# captivate_iso.net
KiCad netlist of a schematic drawn in Altium Designer
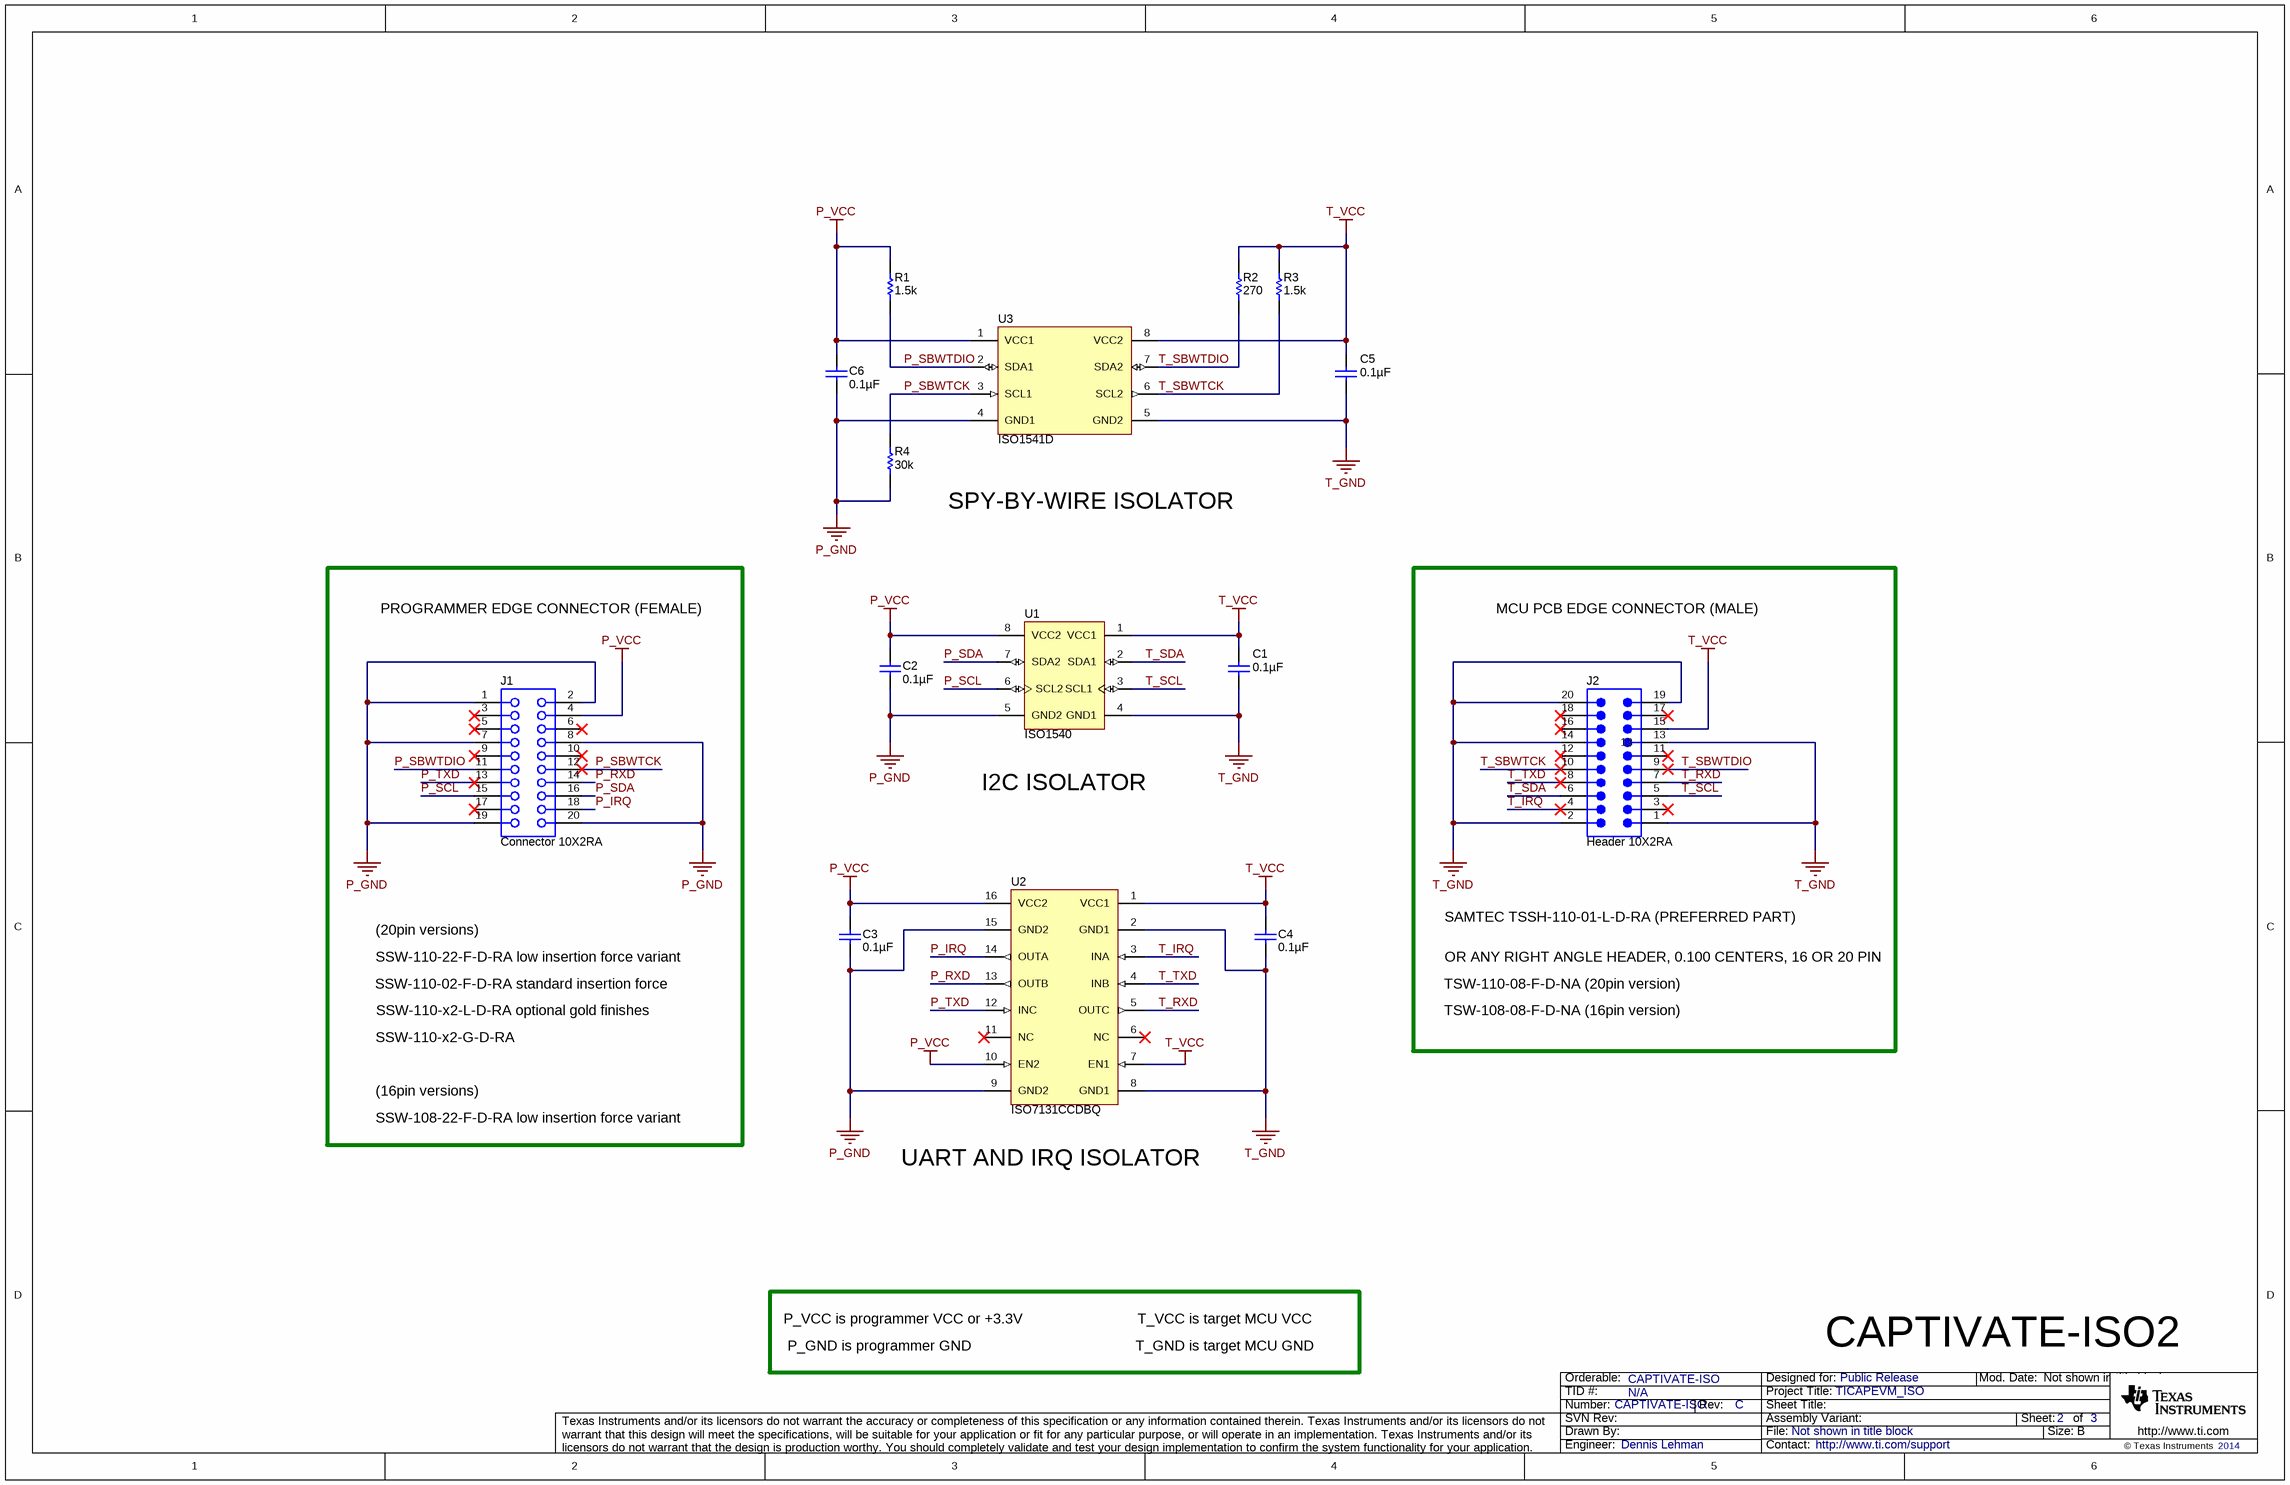
[diagram p0: captivate_iso.SchDoc]

(export (version "E")
  (design (tool "Eeschema 10.0.6"))
  (components
    (comp (ref "C1")
      (value "C1005X5R1A104K")
      (footprint "0402")
      (description "CAP, CERM, 0.1 µF, 10 V, +/- 10%, X5R, 0402")
      (fields
        (field (name "VALUEDISPLAYED") "0.1µF")
        (field (name "MANUFACTURER") "TDK")
        (field (name "PUBLISHER") "Texas Instruments")
      )
      (libsource (lib "Capacitor_Ceramic") (part "C1005X5R1A104K"))
    )
    (comp (ref "C2")
      (value "C1005X5R1A104K")
      (footprint "0402")
      (description "CAP, CERM, 0.1 µF, 10 V, +/- 10%, X5R, 0402")
      (fields
        (field (name "VALUEDISPLAYED") "0.1µF")
        (field (name "MANUFACTURER") "TDK")
        (field (name "PUBLISHER") "Texas Instruments")
      )
      (libsource (lib "Capacitor_Ceramic") (part "C1005X5R1A104K"))
    )
    (comp (ref "C3")
      (value "C1005X5R1A104K")
      (footprint "0402")
      (description "CAP, CERM, 0.1 µF, 10 V, +/- 10%, X5R, 0402")
      (fields
        (field (name "VALUEDISPLAYED") "0.1µF")
        (field (name "MANUFACTURER") "TDK")
        (field (name "PUBLISHER") "Texas Instruments")
      )
      (libsource (lib "Capacitor_Ceramic") (part "C1005X5R1A104K"))
    )
    (comp (ref "C4")
      (value "C1005X5R1A104K")
      (footprint "0402")
      (description "CAP, CERM, 0.1 µF, 10 V, +/- 10%, X5R, 0402")
      (fields
        (field (name "VALUEDISPLAYED") "0.1µF")
        (field (name "MANUFACTURER") "TDK")
        (field (name "PUBLISHER") "Texas Instruments")
      )
      (libsource (lib "Capacitor_Ceramic") (part "C1005X5R1A104K"))
    )
    (comp (ref "C5")
      (value "C1005X5R1A104K")
      (footprint "0402")
      (description "CAP, CERM, 0.1 µF, 10 V, +/- 10%, X5R, 0402")
      (fields
        (field (name "VALUEDISPLAYED") "0.1µF")
        (field (name "MANUFACTURER") "TDK")
        (field (name "PUBLISHER") "Texas Instruments")
      )
      (libsource (lib "Capacitor_Ceramic") (part "C1005X5R1A104K"))
    )
    (comp (ref "C6")
      (value "C1005X5R1A104K")
      (footprint "0402")
      (description "CAP, CERM, 0.1 µF, 10 V, +/- 10%, X5R, 0402")
      (fields
        (field (name "VALUEDISPLAYED") "0.1µF")
        (field (name "MANUFACTURER") "TDK")
        (field (name "PUBLISHER") "Texas Instruments")
      )
      (libsource (lib "Capacitor_Ceramic") (part "C1005X5R1A104K"))
    )
    (comp (ref "J1")
      (value "Connector 10X2RA")
      (footprint "CONN2X10RA")
      (description "Connector, Female, 10-Pin, 2 row, Right Angle")
      (fields
        (field (name "MANUFACTURER") "Samtec")
        (field (name "PARTNUMBER") "SSW-110-22-F-D-RA")
        (field (name "PUBLISHER") "Altium Limited")
      )
      (libsource (lib "Captivate Library") (part "Connector 10X2RA"))
    )
    (comp (ref "J2")
      (value "Header 10X2RA")
      (footprint "HDR2X10RA")
      (description "Header, Male, 10-Pin, 2 row, Shround, Right Angle")
      (fields
        (field (name "MANUFACTURER") "Samtec")
        (field (name "PARTNUMBER") "TSSH-110-01-L-D-RA")
        (field (name "PUBLISHER") "Altium Limited")
      )
      (libsource (lib "Captivate Library") (part "Header 10X2RA"))
    )
    (comp (ref "R1")
      (value "CRCW04021K50JNED")
      (footprint "0402")
      (description "RES, 1.5 k, 5%, 0.063 W, 0402")
      (fields
        (field (name "VALUEDISPLAYED") "1.5k")
        (field (name "MANUFACTURER") "Vishay-Dale")
        (field (name "PUBLISHER") "Texas Instruments")
      )
      (libsource (lib "Resistor_0402") (part "CRCW04021K50JNED"))
    )
    (comp (ref "R2")
      (value "CRCW0402270RJNED")
      (footprint "0402")
      (description "RES, 270, 5%, 0.063 W, 0402")
      (fields
        (field (name "VALUEDISPLAYED") "270")
        (field (name "MANUFACTURER") "Vishay-Dale")
        (field (name "PUBLISHER") "Texas Instruments")
      )
      (libsource (lib "Resistor_0402") (part "CRCW0402270RJNED"))
    )
    (comp (ref "R3")
      (value "CRCW04021K50JNED")
      (footprint "0402")
      (description "RES, 1.5 k, 5%, 0.063 W, 0402")
      (fields
        (field (name "VALUEDISPLAYED") "1.5k")
        (field (name "MANUFACTURER") "Vishay-Dale")
        (field (name "PUBLISHER") "Texas Instruments")
      )
      (libsource (lib "Resistor_0402") (part "CRCW04021K50JNED"))
    )
    (comp (ref "R4")
      (value "CRCW040230K0JNED")
      (footprint "0402")
      (description "RES, 30 k, 5%, 0.063 W, 0402")
      (fields
        (field (name "VALUEDISPLAYED") "30k")
        (field (name "MANUFACTURER") "Vishay-Dale")
        (field (name "PUBLISHER") "Texas Instruments")
      )
      (libsource (lib "Resistor_0402") (part "CRCW040230K0JNED"))
    )
    (comp (ref "U1")
      (value "ISO1540")
      (footprint "D0008A_L")
      (fields
        (field (name "MANUFACTURER") "Texas Instruments")
        (field (name "ALTERNATE PARTNUMBER") "Equivalent")
      )
      (libsource (lib "Captivate Library") (part "ISO1540"))
    )
    (comp (ref "U2")
      (value "ISO7131CCDBQ")
      (footprint "DBQ0016A_N")
      (description "4242-VPK Small-Footprint and Low-Power Triple Channels Digital Isolators, DBQ0016A")
      (fields
        (field (name "MANUFACTURER") "Texas Instruments")
        (field (name "SYMBOLCREATOR") "a0799628")
        (field (name "PUBLISHER") "Texas Instruments")
      )
      (libsource (lib "TI_Pre_Release") (part "ISO7131CCDBQ"))
    )
    (comp (ref "U3")
      (value "ISO1541D")
      (footprint "D0008A_N")
      (description "Low-Power Bidirectional I2C Isolators, D0008A")
      (fields
        (field (name "MANUFACTURER") "Texas Instruments")
        (field (name "SYMBOLCREATOR") "a0411947")
        (field (name "PUBLISHER") "Texas Instruments")
      )
      (libsource (lib "TI_Pre_Release") (part "ISO1541D"))
    )
  )
  (nets
    (net (code "1") (name "/P_IRQ") (class "Default")
      (node (ref "J1") (pin "18") (pinfunction "18_18") (pintype "passive"))
      (node (ref "U2") (pin "14") (pinfunction "OUTA_14") (pintype "output"))
    )
    (net (code "2") (name "/P_RXD") (class "Default")
      (node (ref "J1") (pin "14") (pinfunction "14_14") (pintype "passive"))
      (node (ref "U2") (pin "13") (pinfunction "OUTB_13") (pintype "output"))
    )
    (net (code "3") (name "/P_SBWTCK") (class "Default")
      (node (ref "J1") (pin "12") (pinfunction "12_12") (pintype "passive"))
      (node (ref "R4") (pin "2") (pinfunction "2_2") (pintype "passive"))
      (node (ref "U3") (pin "3") (pinfunction "SCL1_3") (pintype "input"))
    )
    (net (code "4") (name "/P_SBWTDIO") (class "Default")
      (node (ref "J1") (pin "11") (pinfunction "11_11") (pintype "passive"))
      (node (ref "R1") (pin "1") (pinfunction "1_1") (pintype "passive"))
      (node (ref "U3") (pin "2") (pinfunction "SDA1_2") (pintype "bidirectional"))
    )
    (net (code "5") (name "/P_SCL") (class "Default")
      (node (ref "J1") (pin "15") (pinfunction "15_15") (pintype "passive"))
      (node (ref "U1") (pin "6") (pinfunction "SCL2_6") (pintype "bidirectional"))
    )
    (net (code "6") (name "/P_SDA") (class "Default")
      (node (ref "J1") (pin "16") (pinfunction "16_16") (pintype "passive"))
      (node (ref "U1") (pin "7") (pinfunction "SDA2_7") (pintype "bidirectional"))
    )
    (net (code "7") (name "/P_TXD") (class "Default")
      (node (ref "J1") (pin "13") (pinfunction "13_13") (pintype "passive"))
      (node (ref "U2") (pin "12") (pinfunction "INC_12") (pintype "input"))
    )
    (net (code "8") (name "/T_IRQ") (class "Default")
      (node (ref "J2") (pin "4") (pinfunction "4_4") (pintype "passive"))
      (node (ref "U2") (pin "3") (pinfunction "INA_3") (pintype "input"))
    )
    (net (code "9") (name "/T_RXD") (class "Default")
      (node (ref "J2") (pin "7") (pinfunction "7_7") (pintype "passive"))
      (node (ref "U2") (pin "5") (pinfunction "OUTC_5") (pintype "output"))
    )
    (net (code "10") (name "/T_SBWTCK") (class "Default")
      (node (ref "J2") (pin "10") (pinfunction "10_10") (pintype "passive"))
      (node (ref "R3") (pin "1") (pinfunction "1_1") (pintype "passive"))
      (node (ref "U3") (pin "6") (pinfunction "SCL2_6") (pintype "output"))
    )
    (net (code "11") (name "/T_SBWTDIO") (class "Default")
      (node (ref "J2") (pin "9") (pinfunction "9_9") (pintype "passive"))
      (node (ref "R2") (pin "1") (pinfunction "1_1") (pintype "passive"))
      (node (ref "U3") (pin "7") (pinfunction "SDA2_7") (pintype "bidirectional"))
    )
    (net (code "12") (name "/T_SCL") (class "Default")
      (node (ref "J2") (pin "5") (pinfunction "5_5") (pintype "passive"))
      (node (ref "U1") (pin "3") (pinfunction "SCL1_3") (pintype "bidirectional"))
    )
    (net (code "13") (name "/T_SDA") (class "Default")
      (node (ref "J2") (pin "6") (pinfunction "6_6") (pintype "passive"))
      (node (ref "U1") (pin "2") (pinfunction "SDA1_2") (pintype "bidirectional"))
    )
    (net (code "14") (name "/T_TXD") (class "Default")
      (node (ref "J2") (pin "8") (pinfunction "8_8") (pintype "passive"))
      (node (ref "U2") (pin "4") (pinfunction "INB_4") (pintype "input"))
    )
    (net (code "15") (name "P_GND") (class "Default")
      (node (ref "C2") (pin "1") (pinfunction "1_1") (pintype "passive"))
      (node (ref "C3") (pin "1") (pinfunction "1_1") (pintype "passive"))
      (node (ref "C6") (pin "1") (pinfunction "1_1") (pintype "passive"))
      (node (ref "J1") (pin "1") (pinfunction "1_1") (pintype "passive"))
      (node (ref "J1") (pin "19") (pinfunction "19_19") (pintype "passive"))
      (node (ref "J1") (pin "2") (pinfunction "2_2") (pintype "passive"))
      (node (ref "J1") (pin "20") (pinfunction "20_20") (pintype "passive"))
      (node (ref "J1") (pin "7") (pinfunction "7_7") (pintype "passive"))
      (node (ref "J1") (pin "8") (pinfunction "8_8") (pintype "passive"))
      (node (ref "R4") (pin "1") (pinfunction "1_1") (pintype "passive"))
      (node (ref "U1") (pin "5") (pinfunction "GND2_5") (pintype "power_in"))
      (node (ref "U2") (pin "15") (pinfunction "GND2_15") (pintype "power_in"))
      (node (ref "U2") (pin "9") (pinfunction "GND2_9") (pintype "power_in"))
      (node (ref "U3") (pin "4") (pinfunction "GND1_4") (pintype "power_in"))
    )
    (net (code "16") (name "P_VCC") (class "Default")
      (node (ref "C2") (pin "2") (pinfunction "2_2") (pintype "passive"))
      (node (ref "C3") (pin "2") (pinfunction "2_2") (pintype "passive"))
      (node (ref "C6") (pin "2") (pinfunction "2_2") (pintype "passive"))
      (node (ref "J1") (pin "4") (pinfunction "4_4") (pintype "passive"))
      (node (ref "R1") (pin "2") (pinfunction "2_2") (pintype "passive"))
      (node (ref "U1") (pin "8") (pinfunction "VCC2_8") (pintype "power_in"))
      (node (ref "U2") (pin "10") (pinfunction "EN2_10") (pintype "input"))
      (node (ref "U2") (pin "16") (pinfunction "VCC2_16") (pintype "power_in"))
      (node (ref "U3") (pin "1") (pinfunction "VCC1_1") (pintype "power_in"))
    )
    (net (code "17") (name "T_GND") (class "Default")
      (node (ref "C1") (pin "2") (pinfunction "2_2") (pintype "passive"))
      (node (ref "C4") (pin "1") (pinfunction "1_1") (pintype "passive"))
      (node (ref "C5") (pin "2") (pinfunction "2_2") (pintype "passive"))
      (node (ref "J2") (pin "1") (pinfunction "1_1") (pintype "passive"))
      (node (ref "J2") (pin "13") (pinfunction "13_13") (pintype "passive"))
      (node (ref "J2") (pin "14") (pinfunction "14_14") (pintype "passive"))
      (node (ref "J2") (pin "19") (pinfunction "19_19") (pintype "passive"))
      (node (ref "J2") (pin "2") (pinfunction "2_2") (pintype "passive"))
      (node (ref "J2") (pin "20") (pinfunction "20_20") (pintype "passive"))
      (node (ref "U1") (pin "4") (pinfunction "GND1_4") (pintype "power_in"))
      (node (ref "U2") (pin "2") (pinfunction "GND1_2") (pintype "power_in"))
      (node (ref "U2") (pin "8") (pinfunction "GND1_8") (pintype "power_in"))
      (node (ref "U3") (pin "5") (pinfunction "GND2_5") (pintype "power_in"))
    )
    (net (code "18") (name "T_VCC") (class "Default")
      (node (ref "C1") (pin "1") (pinfunction "1_1") (pintype "passive"))
      (node (ref "C4") (pin "2") (pinfunction "2_2") (pintype "passive"))
      (node (ref "C5") (pin "1") (pinfunction "1_1") (pintype "passive"))
      (node (ref "J2") (pin "15") (pinfunction "15_15") (pintype "passive"))
      (node (ref "R2") (pin "2") (pinfunction "2_2") (pintype "passive"))
      (node (ref "R3") (pin "2") (pinfunction "2_2") (pintype "passive"))
      (node (ref "U1") (pin "1") (pinfunction "VCC1_1") (pintype "power_in"))
      (node (ref "U2") (pin "1") (pinfunction "VCC1_1") (pintype "power_in"))
      (node (ref "U2") (pin "7") (pinfunction "EN1_7") (pintype "input"))
      (node (ref "U3") (pin "8") (pinfunction "VCC2_8") (pintype "power_in"))
    )
    (net (code "19") (name "unconnected-(J1-Pad3)") (class "Default")
      (node (ref "J1") (pin "3") (pinfunction "3_3") (pintype "passive+no_connect"))
    )
    (net (code "20") (name "unconnected-(J1-Pad5)") (class "Default")
      (node (ref "J1") (pin "5") (pinfunction "5_5") (pintype "passive+no_connect"))
    )
    (net (code "21") (name "unconnected-(J1-Pad6)") (class "Default")
      (node (ref "J1") (pin "6") (pinfunction "6_6") (pintype "passive+no_connect"))
    )
    (net (code "22") (name "unconnected-(J1-Pad9)") (class "Default")
      (node (ref "J1") (pin "9") (pinfunction "9_9") (pintype "passive+no_connect"))
    )
    (net (code "23") (name "unconnected-(J1-Pad10)") (class "Default")
      (node (ref "J1") (pin "10") (pinfunction "10_10") (pintype "passive+no_connect"))
    )
    (net (code "24") (name "unconnected-(J1-Pad17)") (class "Default")
      (node (ref "J1") (pin "17") (pinfunction "17_17") (pintype "passive+no_connect"))
    )
    (net (code "25") (name "unconnected-(J2-Pad3)") (class "Default")
      (node (ref "J2") (pin "3") (pinfunction "3_3") (pintype "passive+no_connect"))
    )
    (net (code "26") (name "unconnected-(J2-Pad11)") (class "Default")
      (node (ref "J2") (pin "11") (pinfunction "11_11") (pintype "passive+no_connect"))
    )
    (net (code "27") (name "unconnected-(J2-Pad12)") (class "Default")
      (node (ref "J2") (pin "12") (pinfunction "12_12") (pintype "passive+no_connect"))
    )
    (net (code "28") (name "unconnected-(J2-Pad16)") (class "Default")
      (node (ref "J2") (pin "16") (pinfunction "16_16") (pintype "passive+no_connect"))
    )
    (net (code "29") (name "unconnected-(J2-Pad17)") (class "Default")
      (node (ref "J2") (pin "17") (pinfunction "17_17") (pintype "passive+no_connect"))
    )
    (net (code "30") (name "unconnected-(J2-Pad18)") (class "Default")
      (node (ref "J2") (pin "18") (pinfunction "18_18") (pintype "passive+no_connect"))
    )
    (net (code "31") (name "unconnected-(U2-NC-Pad6)") (class "Default")
      (node (ref "U2") (pin "6") (pinfunction "NC_6") (pintype "passive+no_connect"))
    )
    (net (code "32") (name "unconnected-(U2-NC-Pad11)") (class "Default")
      (node (ref "U2") (pin "11") (pinfunction "NC_11") (pintype "passive+no_connect"))
    )
  )
)
